# Akizuki_LCD1602.net
KiCad netlist of a schematic drawn in EAGLE
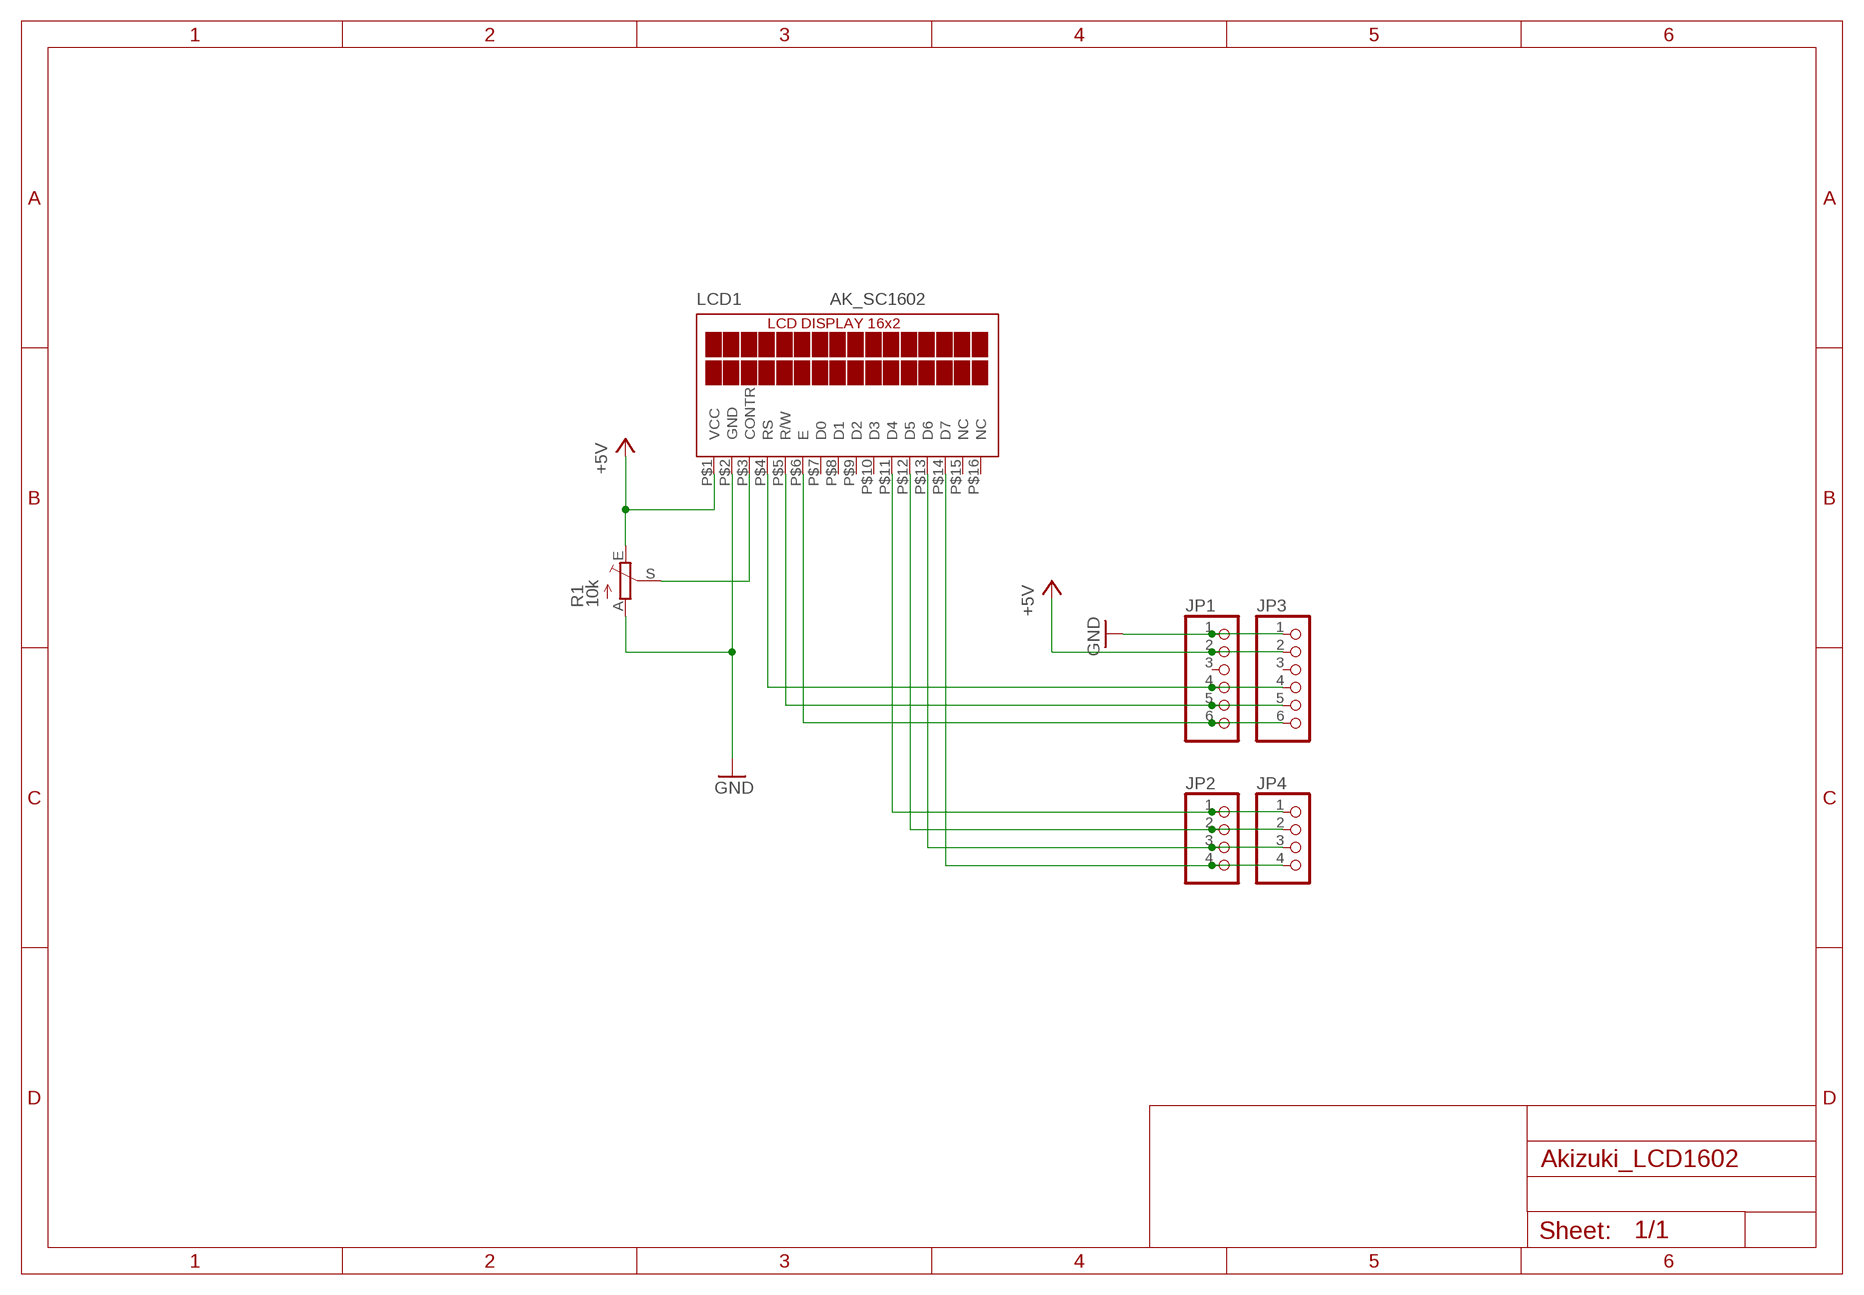
[diagram p0: schematic, sheet 1]

(export (version "E")
  (design (tool "Eeschema 10.0.6"))
  (components
    (comp (ref "JP1")
      (value "PINHD-1X6")
      (footprint "eagle-import:1X06")
      (libsource (lib "eagle-import") (part "PINHD-1X6"))
    )
    (comp (ref "JP2")
      (value "PINHD-1X4")
      (footprint "eagle-import:1X04")
      (libsource (lib "eagle-import") (part "PINHD-1X4"))
    )
    (comp (ref "JP3")
      (value "PINHD-1X6")
      (footprint "eagle-import:1X06")
      (libsource (lib "eagle-import") (part "PINHD-1X6"))
    )
    (comp (ref "JP4")
      (value "PINHD-1X4")
      (footprint "eagle-import:1X04")
      (libsource (lib "eagle-import") (part "PINHD-1X4"))
    )
    (comp (ref "LCD1")
      (value "AK_SC1602")
      (footprint "eagle-import:AK_SC1602")
      (libsource (lib "eagle-import") (part "AK_SC1602"))
    )
    (comp (ref "R1")
      (value "10k")
      (footprint "eagle-import:B25P")
      (libsource (lib "eagle-import") (part "TRIM_EU-B25P"))
    )
  )
  (nets
    (net (code "1") (name "+5V") (class "Default")
      (node (ref "JP1") (pin "2") (pinfunction "2_2") (pintype "passive"))
      (node (ref "JP3") (pin "2") (pinfunction "2_2") (pintype "passive"))
      (node (ref "LCD1") (pin "P$1") (pinfunction "VCC_P$1") (pintype "power_in"))
      (node (ref "R1") (pin "E") (pinfunction "E_E") (pintype "passive"))
    )
    (net (code "2") (name "GND") (class "Default")
      (node (ref "JP1") (pin "1") (pinfunction "1_1") (pintype "passive"))
      (node (ref "JP3") (pin "1") (pinfunction "1_1") (pintype "passive"))
      (node (ref "LCD1") (pin "P$2") (pinfunction "GND_P$2") (pintype "power_in"))
      (node (ref "R1") (pin "A") (pinfunction "A_A") (pintype "passive"))
    )
    (net (code "3") (name "Net-(LCD1-CONTR)") (class "Default")
      (node (ref "LCD1") (pin "P$3") (pinfunction "CONTR_P$3") (pintype "input"))
      (node (ref "R1") (pin "S") (pinfunction "S_S") (pintype "passive"))
    )
    (net (code "4") (name "Net-(LCD1-D4)") (class "Default")
      (node (ref "JP2") (pin "1") (pinfunction "1_1") (pintype "passive"))
      (node (ref "JP4") (pin "1") (pinfunction "1_1") (pintype "passive"))
      (node (ref "LCD1") (pin "P$11") (pinfunction "D4_P$11") (pintype "input"))
    )
    (net (code "5") (name "Net-(LCD1-D5)") (class "Default")
      (node (ref "JP2") (pin "2") (pinfunction "2_2") (pintype "passive"))
      (node (ref "JP4") (pin "2") (pinfunction "2_2") (pintype "passive"))
      (node (ref "LCD1") (pin "P$12") (pinfunction "D5_P$12") (pintype "input"))
    )
    (net (code "6") (name "Net-(LCD1-D6)") (class "Default")
      (node (ref "JP2") (pin "3") (pinfunction "3_3") (pintype "passive"))
      (node (ref "JP4") (pin "3") (pinfunction "3_3") (pintype "passive"))
      (node (ref "LCD1") (pin "P$13") (pinfunction "D6_P$13") (pintype "input"))
    )
    (net (code "7") (name "Net-(LCD1-D7)") (class "Default")
      (node (ref "JP2") (pin "4") (pinfunction "4_4") (pintype "passive"))
      (node (ref "JP4") (pin "4") (pinfunction "4_4") (pintype "passive"))
      (node (ref "LCD1") (pin "P$14") (pinfunction "D7_P$14") (pintype "input"))
    )
    (net (code "8") (name "Net-(LCD1-E)") (class "Default")
      (node (ref "JP1") (pin "6") (pinfunction "6_6") (pintype "passive"))
      (node (ref "JP3") (pin "6") (pinfunction "6_6") (pintype "passive"))
      (node (ref "LCD1") (pin "P$6") (pinfunction "E_P$6") (pintype "input"))
    )
    (net (code "9") (name "Net-(LCD1-RS)") (class "Default")
      (node (ref "JP1") (pin "4") (pinfunction "4_4") (pintype "passive"))
      (node (ref "JP3") (pin "4") (pinfunction "4_4") (pintype "passive"))
      (node (ref "LCD1") (pin "P$4") (pinfunction "RS_P$4") (pintype "input"))
    )
    (net (code "10") (name "Net-(LCD1-R{slash}W)") (class "Default")
      (node (ref "JP1") (pin "5") (pinfunction "5_5") (pintype "passive"))
      (node (ref "JP3") (pin "5") (pinfunction "5_5") (pintype "passive"))
      (node (ref "LCD1") (pin "P$5") (pinfunction "R/W_P$5") (pintype "input"))
    )
    (net (code "11") (name "unconnected-(JP1-Pad3)") (class "Default")
      (node (ref "JP1") (pin "3") (pinfunction "3_3") (pintype "passive"))
    )
    (net (code "12") (name "unconnected-(JP3-Pad3)") (class "Default")
      (node (ref "JP3") (pin "3") (pinfunction "3_3") (pintype "passive"))
    )
    (net (code "13") (name "unconnected-(LCD1-D0-PadP$7)") (class "Default")
      (node (ref "LCD1") (pin "P$7") (pinfunction "D0_P$7") (pintype "input"))
    )
    (net (code "14") (name "unconnected-(LCD1-D1-PadP$8)") (class "Default")
      (node (ref "LCD1") (pin "P$8") (pinfunction "D1_P$8") (pintype "input"))
    )
    (net (code "15") (name "unconnected-(LCD1-D2-PadP$9)") (class "Default")
      (node (ref "LCD1") (pin "P$9") (pinfunction "D2_P$9") (pintype "input"))
    )
    (net (code "16") (name "unconnected-(LCD1-D3-PadP$10)") (class "Default")
      (node (ref "LCD1") (pin "P$10") (pinfunction "D3_P$10") (pintype "input"))
    )
    (net (code "17") (name "unconnected-(LCD1-NC-PadP$15)") (class "Default")
      (node (ref "LCD1") (pin "P$15") (pinfunction "NC_P$15") (pintype "no_connect"))
    )
    (net (code "18") (name "unconnected-(LCD1-NC-PadP$16)") (class "Default")
      (node (ref "LCD1") (pin "P$16") (pinfunction "NC_P$16") (pintype "no_connect"))
    )
  )
)
